# ESP32.net
KiCad netlist of a schematic drawn in Altium Designer
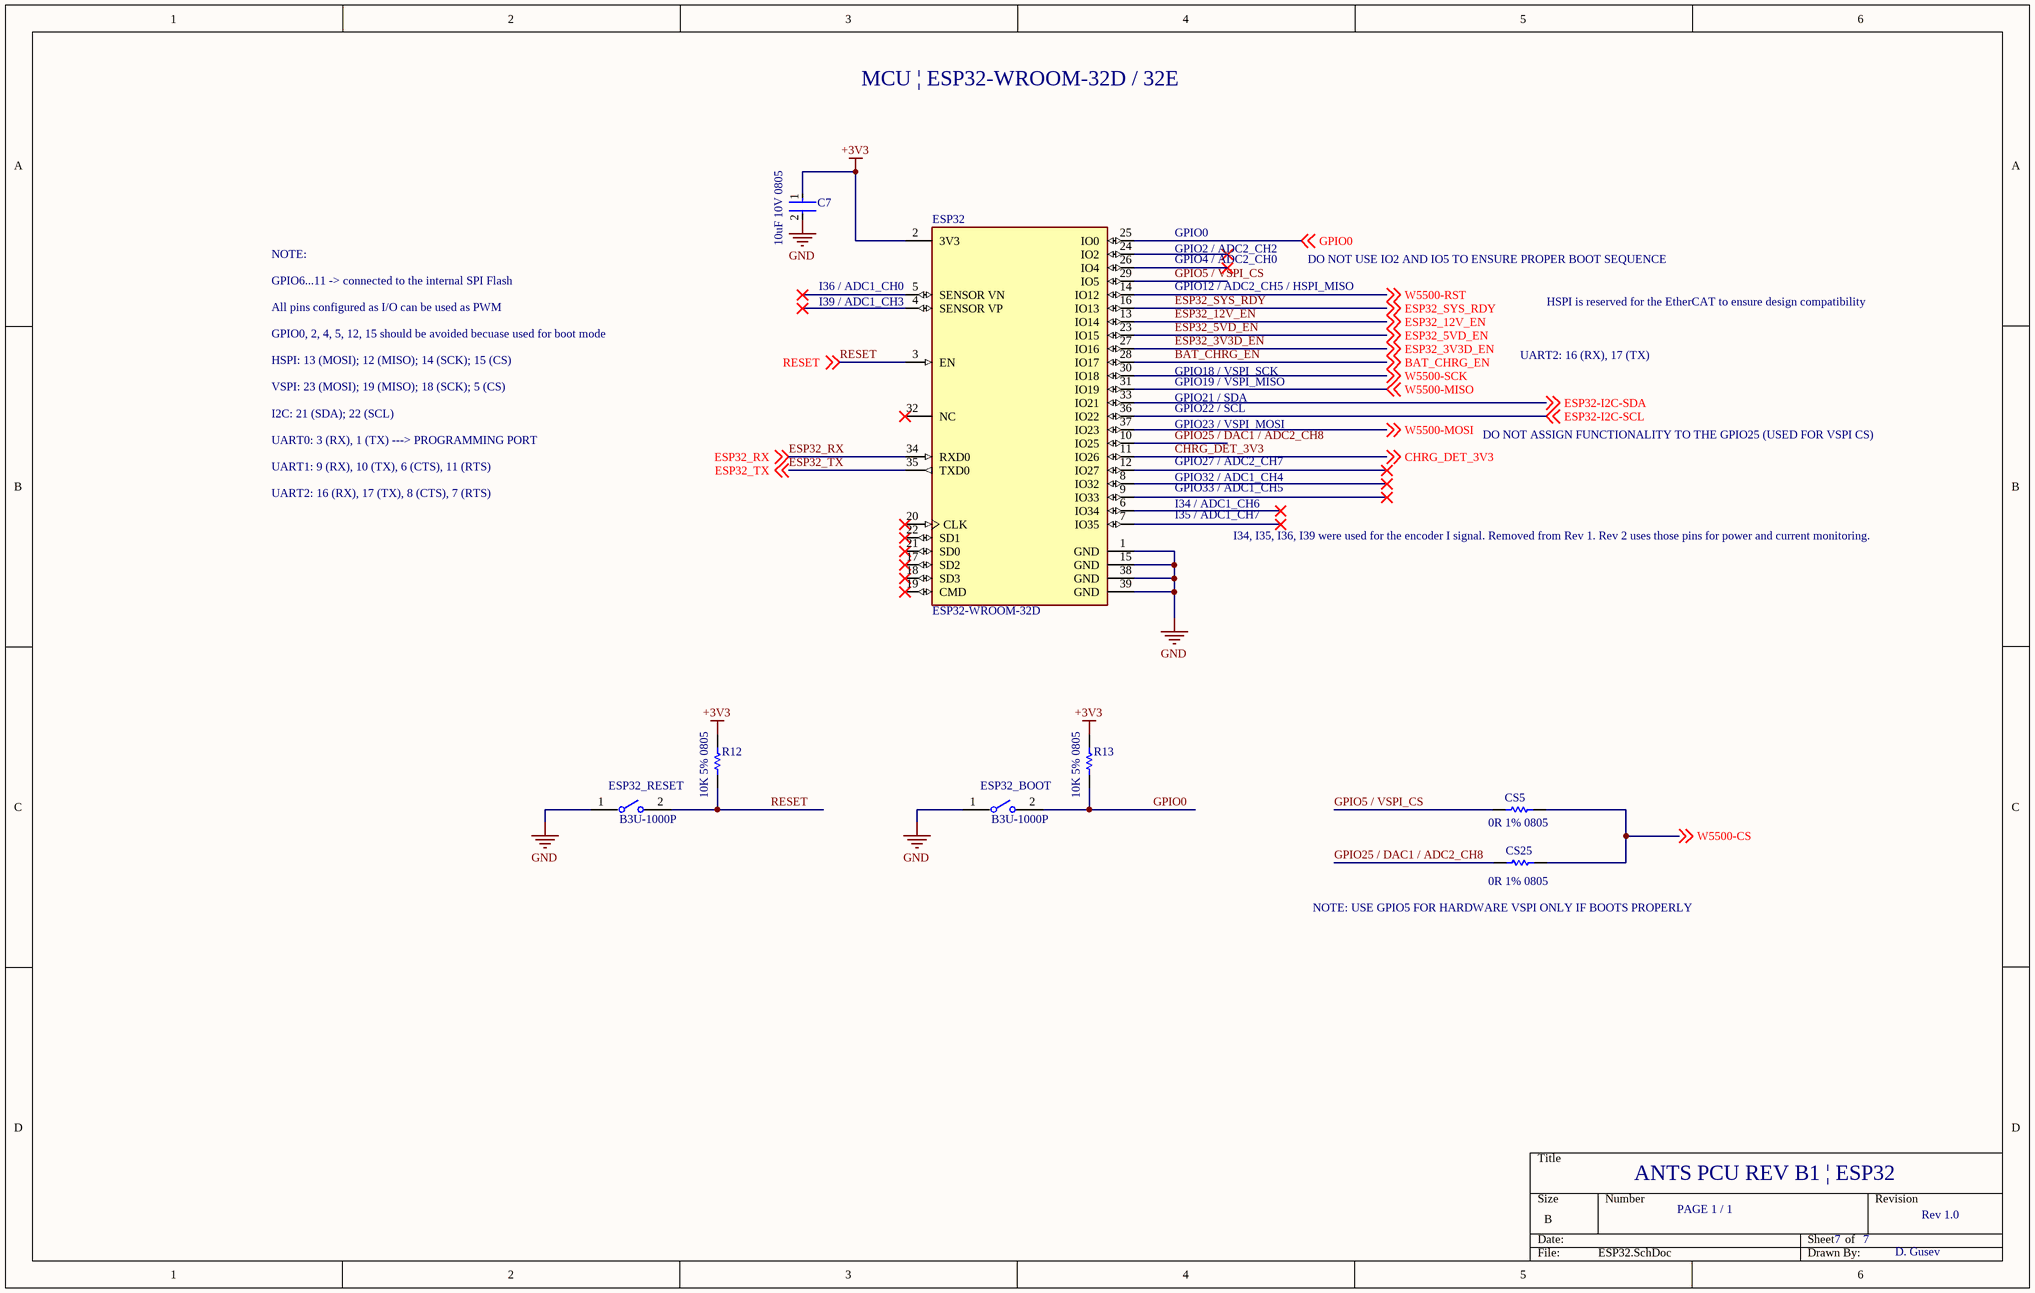
[diagram p0: ESP32.SchDoc]

(export (version "E")
  (design (tool "Eeschema 10.0.6"))
  (components
    (comp (ref "C7")
      (value "10uF 10V 0805")
      (footprint "FP-C0805C-DG-MFG")
      (description "CAP CER 10UF 10V X5R 0805")
      (fields (field (name "TOLERANCE") "10%") (field (name "MANUFACTURER PART NUMBER") "C0805C106K8PACTU"))
      (libsource (lib "Altium Content Vault") (part "11868f565c42a9108669ba33697ecf6"))
    )
    (comp (ref "CS5")
      (value "0R 1% 0805")
      (footprint "RESC2013X60X35LL10T20")
      (description "Chip Resistor, 1 Ohm, +/- 1%, 125 mW, -55 to 155 degC, 0805 (2012 Metric), RoHS, Tape and Reel")
      (fields (field (name "MANUFACTURER") "Yageo"))
      (libsource (lib "Altium Content Vault") (part "RES-2"))
    )
    (comp (ref "CS25")
      (value "0R 1% 0805")
      (footprint "RESC2013X60X35LL10T20")
      (description "Chip Resistor, 1 Ohm, +/- 1%, 125 mW, -55 to 155 degC, 0805 (2012 Metric), RoHS, Tape and Reel")
      (fields (field (name "MANUFACTURER") "Yageo"))
      (libsource (lib "Altium Content Vault") (part "RES-2"))
    )
    (comp (ref "ESP32")
      (value "ESP32-WROOM-32D")
      (footprint "FP-ESP32-WROOM-32D-MFG")
      (description "WIFI MODULE 32MBITS SPI FLASH")
      (fields
        (field (name "OCTOPART") "https://octopart.com/esp32-wroom-32d-espressif+systems-91040050")
        (field (name "MANUFACTURER") "Espressif Systems")
      )
      (libsource (lib "Altium Content Vault") (part "a031a76f8c27026a7a7f4657ff233a3"))
    )
    (comp (ref "ESP32_BOOT")
      (value "B3U-1000P")
      (footprint "FP-B3U-1000P-MFG")
      (description "SWITCH TACTILE SPST-NO 0.05A 12V")
      (libsource (lib "Altium Content Vault") (part "ae622034201233ca1abcedc05908f33"))
    )
    (comp (ref "ESP32_RESET")
      (value "B3U-1000P")
      (footprint "FP-B3U-1000P-MFG")
      (description "SWITCH TACTILE SPST-NO 0.05A 12V")
      (libsource (lib "Altium Content Vault") (part "ae622034201233ca1abcedc05908f33"))
    )
    (comp (ref "R12")
      (value "10K 5% 0805")
      (footprint "RESC2013X60X40ML20T25")
      (fields (field (name "PART NUMBER") "ERA6AEB123V") (field (name "MANUFACTURER") "Panasonic"))
      (libsource (lib "Altium Content Vault") (part "RES"))
    )
    (comp (ref "R13")
      (value "10K 5% 0805")
      (footprint "RESC2013X60X40ML20T25")
      (fields (field (name "PART NUMBER") "ERA6AEB123V") (field (name "MANUFACTURER") "Panasonic"))
      (libsource (lib "Altium Content Vault") (part "RES"))
    )
  )
  (nets
    (net (code "1") (name "+3V3") (class "Default")
      (node (ref "C7") (pin "1") (pinfunction "1_1") (pintype "passive"))
      (node (ref "ESP32") (pin "2") (pinfunction "3V3_2") (pintype "power_in"))
      (node (ref "R12") (pin "2") (pinfunction "2_2") (pintype "passive"))
      (node (ref "R13") (pin "2") (pinfunction "2_2") (pintype "passive"))
    )
    (net (code "2") (name "/GPIO5 {slash} VSPI_CS") (class "Default")
      (node (ref "CS5") (pin "1") (pinfunction "1_1") (pintype "passive"))
      (node (ref "ESP32") (pin "29") (pinfunction "IO5_29") (pintype "bidirectional"))
    )
    (net (code "3") (name "/GPIO25 {slash} DAC1 {slash} ADC2_CH8") (class "Default")
      (node (ref "CS25") (pin "1") (pinfunction "1_1") (pintype "passive"))
      (node (ref "ESP32") (pin "10") (pinfunction "IO25_10") (pintype "bidirectional"))
    )
    (net (code "4") (name "BAT_CHRG_EN") (class "Default")
      (node (ref "ESP32") (pin "28") (pinfunction "IO17_28") (pintype "bidirectional"))
    )
    (net (code "5") (name "CHRG_DET_3V3") (class "Default")
      (node (ref "ESP32") (pin "11") (pinfunction "IO26_11") (pintype "bidirectional"))
    )
    (net (code "6") (name "ESP32-I2C-SCL") (class "Default")
      (node (ref "ESP32") (pin "36") (pinfunction "IO22_36") (pintype "bidirectional"))
    )
    (net (code "7") (name "ESP32-I2C-SDA") (class "Default")
      (node (ref "ESP32") (pin "33") (pinfunction "IO21_33") (pintype "bidirectional"))
    )
    (net (code "8") (name "ESP32_3V3D_EN") (class "Default")
      (node (ref "ESP32") (pin "27") (pinfunction "IO16_27") (pintype "bidirectional"))
    )
    (net (code "9") (name "ESP32_5VD_EN") (class "Default")
      (node (ref "ESP32") (pin "23") (pinfunction "IO15_23") (pintype "bidirectional"))
    )
    (net (code "10") (name "ESP32_12V_EN") (class "Default")
      (node (ref "ESP32") (pin "13") (pinfunction "IO14_13") (pintype "bidirectional"))
    )
    (net (code "11") (name "ESP32_RX") (class "Default")
      (node (ref "ESP32") (pin "34") (pinfunction "RXD0_34") (pintype "input"))
    )
    (net (code "12") (name "ESP32_SYS_RDY") (class "Default")
      (node (ref "ESP32") (pin "16") (pinfunction "IO13_16") (pintype "bidirectional"))
    )
    (net (code "13") (name "ESP32_TX") (class "Default")
      (node (ref "ESP32") (pin "35") (pinfunction "TXD0_35") (pintype "output"))
    )
    (net (code "14") (name "GND") (class "Default")
      (node (ref "C7") (pin "2") (pinfunction "2_2") (pintype "passive"))
      (node (ref "ESP32") (pin "1") (pinfunction "GND_1") (pintype "power_in"))
      (node (ref "ESP32") (pin "15") (pinfunction "GND_15") (pintype "power_in"))
      (node (ref "ESP32") (pin "38") (pinfunction "GND_38") (pintype "power_in"))
      (node (ref "ESP32") (pin "39") (pinfunction "GND_39") (pintype "power_in"))
      (node (ref "ESP32_BOOT") (pin "1") (pinfunction "1_1") (pintype "passive"))
      (node (ref "ESP32_RESET") (pin "1") (pinfunction "1_1") (pintype "passive"))
    )
    (net (code "15") (name "GPIO0") (class "Default")
      (node (ref "ESP32") (pin "25") (pinfunction "IO0_25") (pintype "bidirectional"))
      (node (ref "ESP32_BOOT") (pin "2") (pinfunction "2_2") (pintype "passive"))
      (node (ref "R13") (pin "1") (pinfunction "1_1") (pintype "passive"))
    )
    (net (code "16") (name "RESET") (class "Default")
      (node (ref "ESP32") (pin "3") (pinfunction "EN_3") (pintype "input"))
      (node (ref "ESP32_RESET") (pin "2") (pinfunction "2_2") (pintype "passive"))
      (node (ref "R12") (pin "1") (pinfunction "1_1") (pintype "passive"))
    )
    (net (code "17") (name "W5500-CS") (class "Default")
      (node (ref "CS25") (pin "2") (pinfunction "2_2") (pintype "passive"))
      (node (ref "CS5") (pin "2") (pinfunction "2_2") (pintype "passive"))
    )
    (net (code "18") (name "W5500-MISO") (class "Default")
      (node (ref "ESP32") (pin "31") (pinfunction "IO19_31") (pintype "bidirectional"))
    )
    (net (code "19") (name "W5500-MOSI") (class "Default")
      (node (ref "ESP32") (pin "37") (pinfunction "IO23_37") (pintype "bidirectional"))
    )
    (net (code "20") (name "W5500-RST") (class "Default")
      (node (ref "ESP32") (pin "14") (pinfunction "IO12_14") (pintype "bidirectional"))
    )
    (net (code "21") (name "W5500-SCK") (class "Default")
      (node (ref "ESP32") (pin "30") (pinfunction "IO18_30") (pintype "bidirectional"))
    )
    (net (code "22") (name "unconnected-(ESP32-CLK-Pad20)") (class "Default")
      (node (ref "ESP32") (pin "20") (pinfunction "CLK_20") (pintype "input+no_connect"))
    )
    (net (code "23") (name "unconnected-(ESP32-CMD-Pad19)") (class "Default")
      (node (ref "ESP32") (pin "19") (pinfunction "CMD_19") (pintype "bidirectional+no_connect"))
    )
    (net (code "24") (name "unconnected-(ESP32-IO2-Pad24)") (class "Default")
      (node (ref "ESP32") (pin "24") (pinfunction "IO2_24") (pintype "bidirectional+no_connect"))
    )
    (net (code "25") (name "unconnected-(ESP32-IO4-Pad26)") (class "Default")
      (node (ref "ESP32") (pin "26") (pinfunction "IO4_26") (pintype "bidirectional+no_connect"))
    )
    (net (code "26") (name "unconnected-(ESP32-IO27-Pad12)") (class "Default")
      (node (ref "ESP32") (pin "12") (pinfunction "IO27_12") (pintype "bidirectional+no_connect"))
    )
    (net (code "27") (name "unconnected-(ESP32-IO32-Pad8)") (class "Default")
      (node (ref "ESP32") (pin "8") (pinfunction "IO32_8") (pintype "bidirectional+no_connect"))
    )
    (net (code "28") (name "unconnected-(ESP32-IO33-Pad9)") (class "Default")
      (node (ref "ESP32") (pin "9") (pinfunction "IO33_9") (pintype "bidirectional+no_connect"))
    )
    (net (code "29") (name "unconnected-(ESP32-IO34-Pad6)") (class "Default")
      (node (ref "ESP32") (pin "6") (pinfunction "IO34_6") (pintype "bidirectional+no_connect"))
    )
    (net (code "30") (name "unconnected-(ESP32-IO35-Pad7)") (class "Default")
      (node (ref "ESP32") (pin "7") (pinfunction "IO35_7") (pintype "bidirectional+no_connect"))
    )
    (net (code "31") (name "unconnected-(ESP32-NC-Pad32)") (class "Default")
      (node (ref "ESP32") (pin "32") (pinfunction "NC_32") (pintype "passive+no_connect"))
    )
    (net (code "32") (name "unconnected-(ESP32-SD0-Pad21)") (class "Default")
      (node (ref "ESP32") (pin "21") (pinfunction "SD0_21") (pintype "bidirectional+no_connect"))
    )
    (net (code "33") (name "unconnected-(ESP32-SD1-Pad22)") (class "Default")
      (node (ref "ESP32") (pin "22") (pinfunction "SD1_22") (pintype "bidirectional+no_connect"))
    )
    (net (code "34") (name "unconnected-(ESP32-SD2-Pad17)") (class "Default")
      (node (ref "ESP32") (pin "17") (pinfunction "SD2_17") (pintype "bidirectional+no_connect"))
    )
    (net (code "35") (name "unconnected-(ESP32-SD3-Pad18)") (class "Default")
      (node (ref "ESP32") (pin "18") (pinfunction "SD3_18") (pintype "bidirectional+no_connect"))
    )
    (net (code "36") (name "unconnected-(ESP32-SENSOR_VN-Pad5)") (class "Default")
      (node (ref "ESP32") (pin "5") (pinfunction "SENSOR_VN_5") (pintype "bidirectional+no_connect"))
    )
    (net (code "37") (name "unconnected-(ESP32-SENSOR_VP-Pad4)") (class "Default")
      (node (ref "ESP32") (pin "4") (pinfunction "SENSOR_VP_4") (pintype "bidirectional+no_connect"))
    )
  )
)
